# snappergps_board_2_2_0.net
KiCad netlist of a schematic drawn in EAGLE
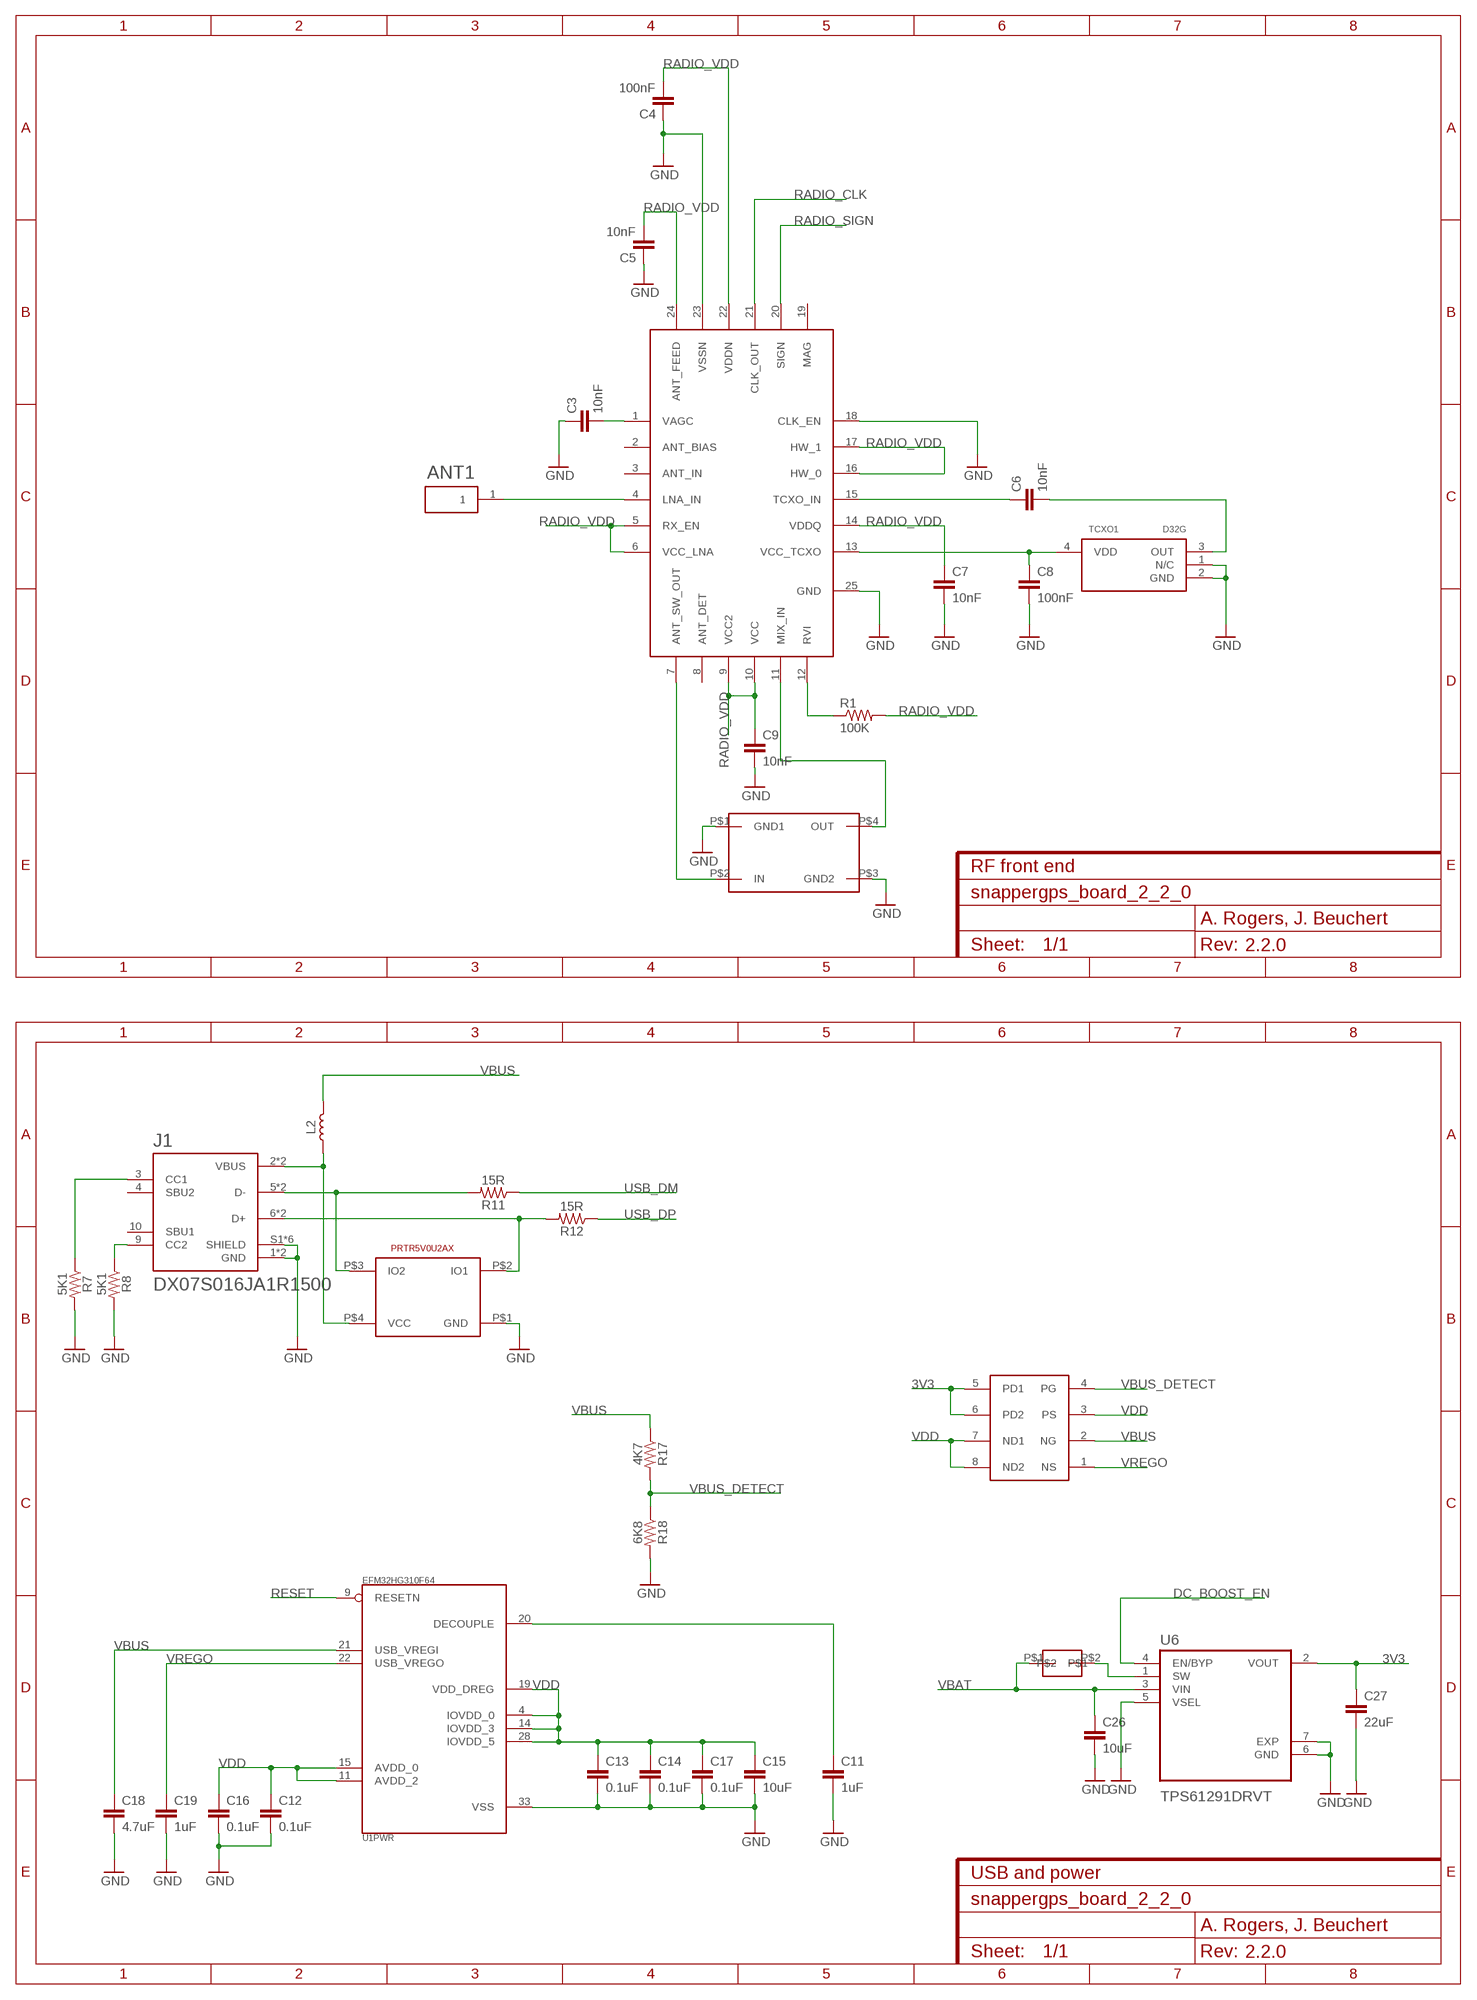
[diagram p0: schematic, sheet 1, part 1 of 2]
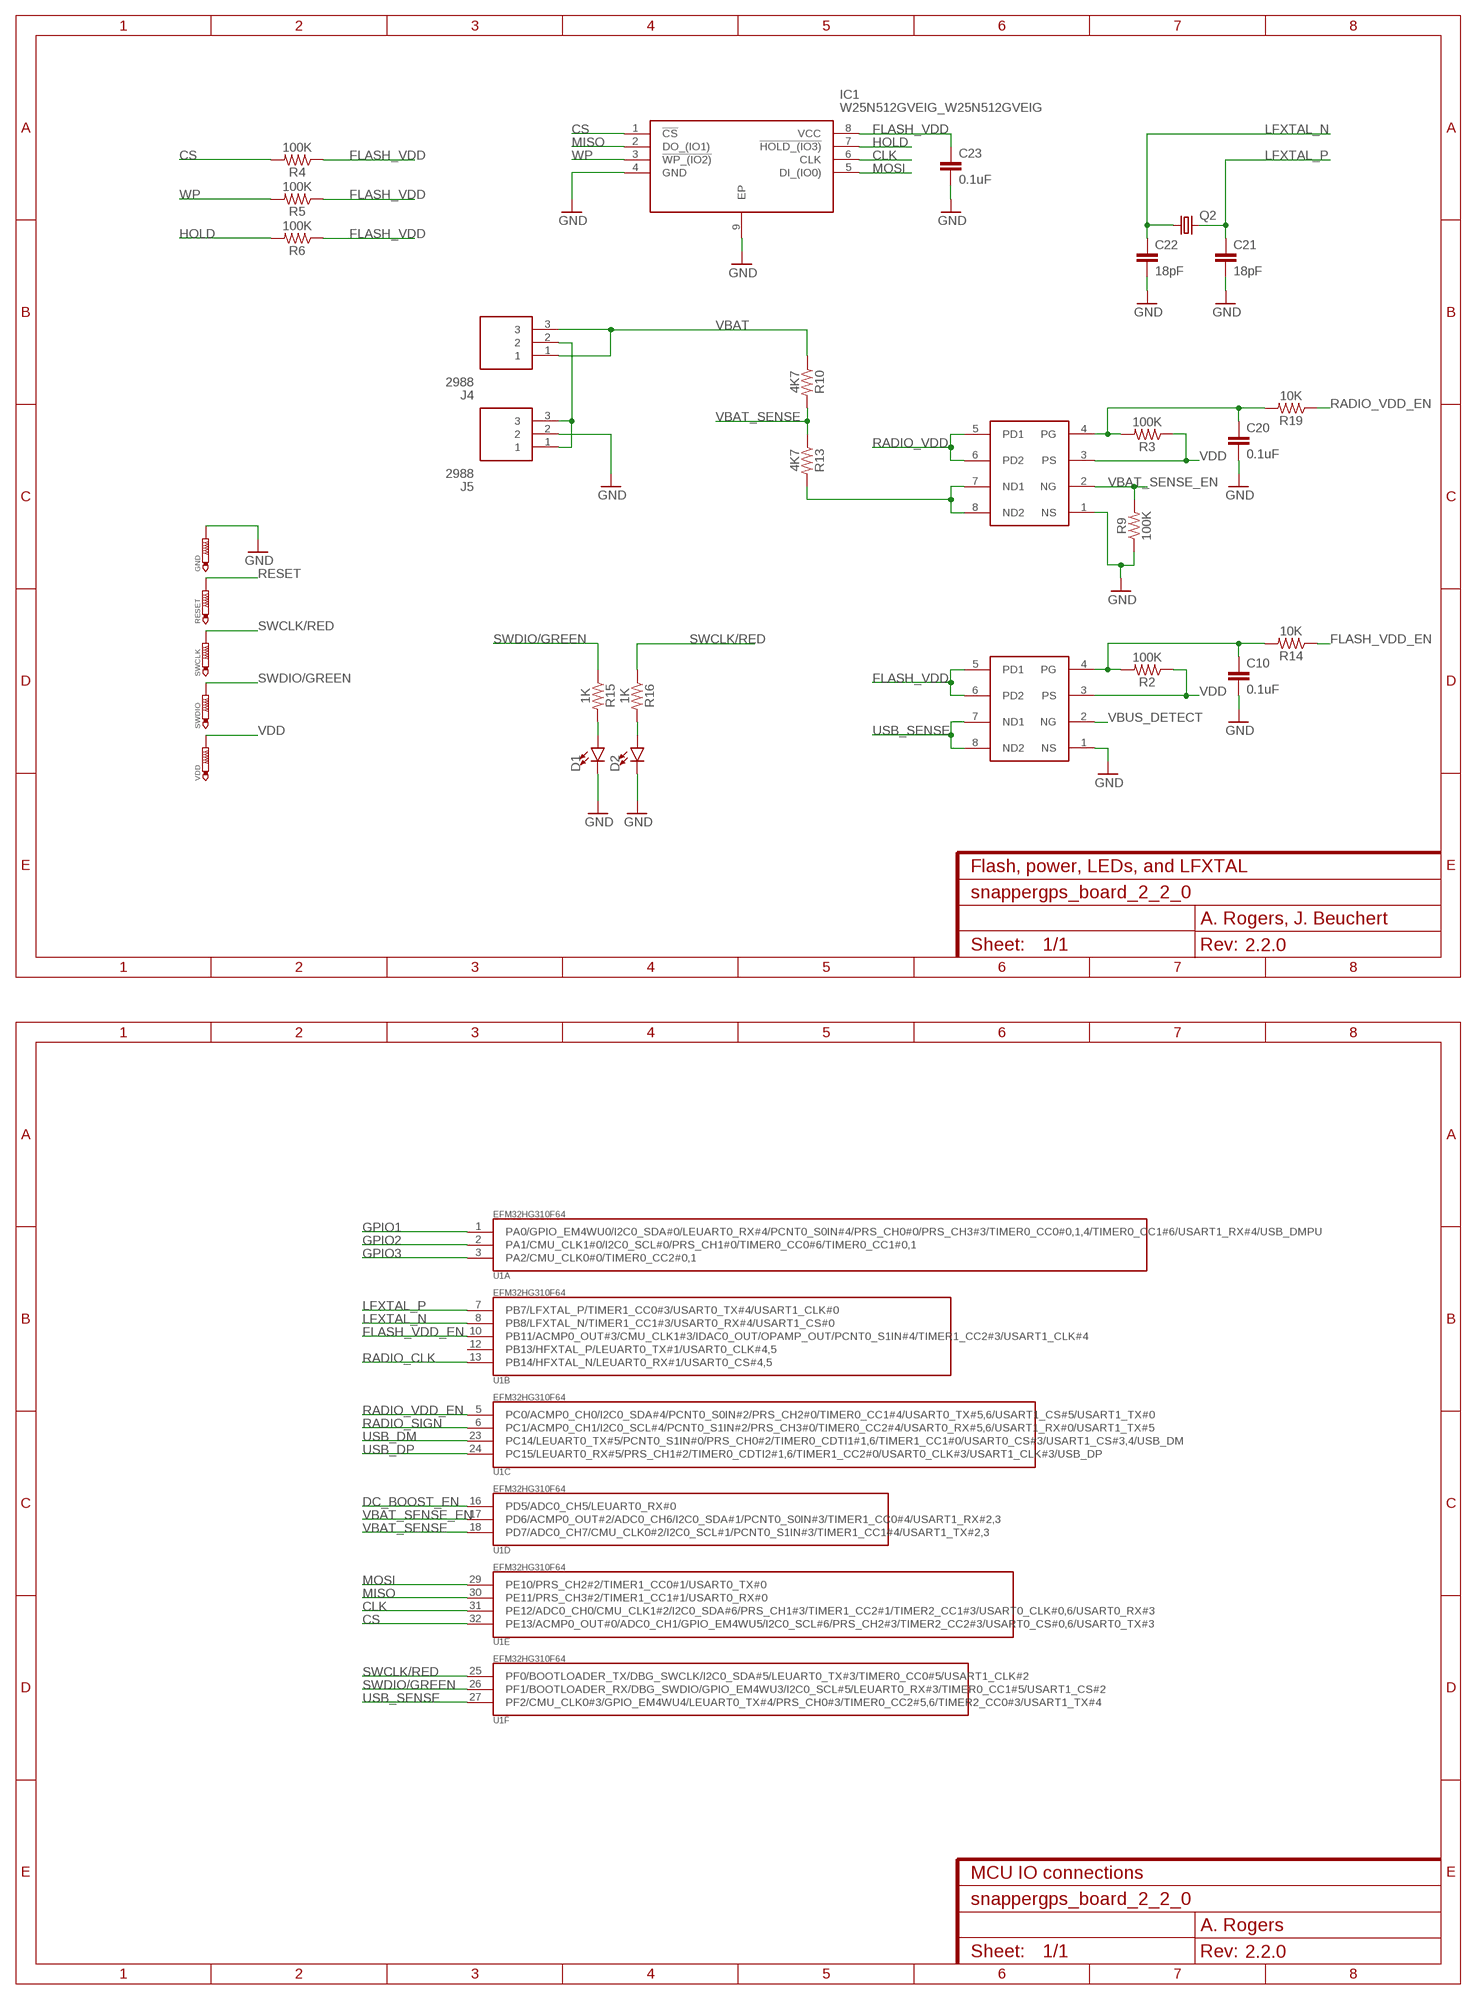
[diagram p1: schematic, sheet 1, part 2 of 2]

(export (version "E")
  (design (tool "Eeschema 10.0.6"))
  (components
    (comp (ref "ANT1")
      (value "GP.1575.25.2.A.02")
      (footprint "eagle-import:GP1575252A02")
      (fields (field (name "MOUSER_PART_NUMBER") "960-GP1575252A02"))
      (libsource (lib "eagle-import") (part "GP.1575.25.2.A.02"))
    )
    (comp (ref "C3")
      (value "10nF")
      (footprint "eagle-import:0402")
      (libsource (lib "eagle-import") (part "CAPACITOR_0402"))
    )
    (comp (ref "C4")
      (value "100nF")
      (footprint "eagle-import:0402")
      (libsource (lib "eagle-import") (part "CAPACITOR_0402"))
    )
    (comp (ref "C5")
      (value "10nF")
      (footprint "eagle-import:0402")
      (libsource (lib "eagle-import") (part "CAPACITOR_0402"))
    )
    (comp (ref "C6")
      (value "10nF")
      (footprint "eagle-import:0402")
      (libsource (lib "eagle-import") (part "CAPACITOR_0402"))
    )
    (comp (ref "C7")
      (value "10nF")
      (footprint "eagle-import:0402")
      (libsource (lib "eagle-import") (part "CAPACITOR_0402"))
    )
    (comp (ref "C8")
      (value "100nF")
      (footprint "eagle-import:0402")
      (libsource (lib "eagle-import") (part "CAPACITOR_0402"))
    )
    (comp (ref "C9")
      (value "10nF")
      (footprint "eagle-import:0402")
      (libsource (lib "eagle-import") (part "CAPACITOR_0402"))
    )
    (comp (ref "C10")
      (value "0.1uF")
      (footprint "eagle-import:0402")
      (libsource (lib "eagle-import") (part "CAPACITOR_0402"))
    )
    (comp (ref "C11")
      (value "1uF")
      (footprint "eagle-import:0603")
      (libsource (lib "eagle-import") (part "CAPACITOR_0603"))
    )
    (comp (ref "C12")
      (value "0.1uF")
      (footprint "eagle-import:0402")
      (libsource (lib "eagle-import") (part "CAPACITOR_0402"))
    )
    (comp (ref "C13")
      (value "0.1uF")
      (footprint "eagle-import:0402")
      (libsource (lib "eagle-import") (part "CAPACITOR_0402"))
    )
    (comp (ref "C14")
      (value "0.1uF")
      (footprint "eagle-import:0402")
      (libsource (lib "eagle-import") (part "CAPACITOR_0402"))
    )
    (comp (ref "C15")
      (value "10uF")
      (footprint "eagle-import:0603")
      (libsource (lib "eagle-import") (part "CAPACITOR_0603"))
    )
    (comp (ref "C16")
      (value "0.1uF")
      (footprint "eagle-import:0402")
      (libsource (lib "eagle-import") (part "CAPACITOR_0402"))
    )
    (comp (ref "C17")
      (value "0.1uF")
      (footprint "eagle-import:0402")
      (libsource (lib "eagle-import") (part "CAPACITOR_0402"))
    )
    (comp (ref "C18")
      (value "4.7uF")
      (footprint "eagle-import:0603")
      (libsource (lib "eagle-import") (part "CAPACITOR_0603"))
    )
    (comp (ref "C19")
      (value "1uF")
      (footprint "eagle-import:0603")
      (libsource (lib "eagle-import") (part "CAPACITOR_0603"))
    )
    (comp (ref "C20")
      (value "0.1uF")
      (footprint "eagle-import:0402")
      (libsource (lib "eagle-import") (part "CAPACITOR_0402"))
    )
    (comp (ref "C21")
      (value "18pF")
      (footprint "eagle-import:0402")
      (libsource (lib "eagle-import") (part "CAPACITOR_0402"))
    )
    (comp (ref "C22")
      (value "18pF")
      (footprint "eagle-import:0402")
      (libsource (lib "eagle-import") (part "CAPACITOR_0402"))
    )
    (comp (ref "C23")
      (value "0.1uF")
      (footprint "eagle-import:0402")
      (libsource (lib "eagle-import") (part "CAPACITOR_0402"))
    )
    (comp (ref "C26")
      (value "10uF")
      (footprint "eagle-import:C0603K")
      (libsource (lib "eagle-import") (part "C-EUC0603K"))
    )
    (comp (ref "C27")
      (value "22uF")
      (footprint "eagle-import:C0603K")
      (libsource (lib "eagle-import") (part "C-EUC0603K"))
    )
    (comp (ref "D1")
      (value "LED0603")
      (footprint "eagle-import:LED-0603")
      (libsource (lib "eagle-import") (part "LED0603"))
    )
    (comp (ref "D2")
      (value "LED0603")
      (footprint "eagle-import:LED-0603")
      (libsource (lib "eagle-import") (part "LED0603"))
    )
    (comp (ref "GND")
      (value "PTR1B1,27")
      (footprint "eagle-import:B1,27")
      (libsource (lib "eagle-import") (part "PTR1B1,27"))
    )
    (comp (ref "IC1")
      (value "W25N512GVEIG_W25N512GVEIG")
      (footprint "eagle-import:W25N512GVEIG_SON127P800X600X80-9N")
      (fields
        (field (name "MANUFACTURER_PART_NUMBER") "W25N512GVEIG")
        (field (name "MOUSER_PART_NUMBER") "454-W25N512GVEIG")
      )
      (libsource (lib "eagle-import") (part "W25N512GVEIG_W25N512GVEIG"))
    )
    (comp (ref "J1")
      (value "DX07S016JA1R1500")
      (footprint "eagle-import:JAE_DX07S016JA1R1500")
      (fields (field (name "MF") "JAE Electronics"))
      (libsource (lib "eagle-import") (part "DX07S016JA1R1500"))
    )
    (comp (ref "J4")
      (value "2988")
      (footprint "eagle-import:2988")
      (fields (field (name "MOUSER_PART_NUMBER") "534-2988"))
      (libsource (lib "eagle-import") (part "2988"))
    )
    (comp (ref "J5")
      (value "2988")
      (footprint "eagle-import:2988")
      (fields (field (name "MOUSER_PART_NUMBER") "534-2988"))
      (libsource (lib "eagle-import") (part "2988"))
    )
    (comp (ref "L2")
      (value "INDUCTOR")
      (footprint "eagle-import:0402")
      (libsource (lib "eagle-import") (part "INDUCTOR"))
    )
    (comp (ref "Q1")
      (value "TT8M1TRAMANDA")
      (footprint "eagle-import:AMANDA_TSST8")
      (libsource (lib "eagle-import") (part "TT8M1TRAMANDA"))
    )
    (comp (ref "Q2")
      (value "CRYSTAL_JTX310")
      (footprint "eagle-import:3.2X1.5")
      (libsource (lib "eagle-import") (part "CRYSTAL_JTX310"))
    )
    (comp (ref "Q3")
      (value "TT8M1TRAMANDA")
      (footprint "eagle-import:AMANDA_TSST8")
      (libsource (lib "eagle-import") (part "TT8M1TRAMANDA"))
    )
    (comp (ref "Q4")
      (value "TT8M1TRAMANDA")
      (footprint "eagle-import:AMANDA_TSST8")
      (libsource (lib "eagle-import") (part "TT8M1TRAMANDA"))
    )
    (comp (ref "R1")
      (value "100K")
      (footprint "eagle-import:0402")
      (libsource (lib "eagle-import") (part "RESISTOR_0402"))
    )
    (comp (ref "R2")
      (value "100K")
      (footprint "eagle-import:0402")
      (libsource (lib "eagle-import") (part "RESISTOR_0402"))
    )
    (comp (ref "R3")
      (value "100K")
      (footprint "eagle-import:0402")
      (libsource (lib "eagle-import") (part "RESISTOR_0402"))
    )
    (comp (ref "R4")
      (value "100K")
      (footprint "eagle-import:0402")
      (libsource (lib "eagle-import") (part "RESISTOR_0402"))
    )
    (comp (ref "R5")
      (value "100K")
      (footprint "eagle-import:0402")
      (libsource (lib "eagle-import") (part "RESISTOR_0402"))
    )
    (comp (ref "R6")
      (value "100K")
      (footprint "eagle-import:0402")
      (libsource (lib "eagle-import") (part "RESISTOR_0402"))
    )
    (comp (ref "R7")
      (value "5K1")
      (footprint "eagle-import:0402")
      (libsource (lib "eagle-import") (part "RESISTOR_0402"))
    )
    (comp (ref "R8")
      (value "5K1")
      (footprint "eagle-import:0402")
      (libsource (lib "eagle-import") (part "RESISTOR_0402"))
    )
    (comp (ref "R9")
      (value "100K")
      (footprint "eagle-import:0402")
      (libsource (lib "eagle-import") (part "RESISTOR_0402"))
    )
    (comp (ref "R10")
      (value "4K7")
      (footprint "eagle-import:0402")
      (libsource (lib "eagle-import") (part "RESISTOR_0402"))
    )
    (comp (ref "R11")
      (value "15R")
      (footprint "eagle-import:0402")
      (libsource (lib "eagle-import") (part "RESISTOR_0402"))
    )
    (comp (ref "R12")
      (value "15R")
      (footprint "eagle-import:0402")
      (libsource (lib "eagle-import") (part "RESISTOR_0402"))
    )
    (comp (ref "R13")
      (value "4K7")
      (footprint "eagle-import:0402")
      (libsource (lib "eagle-import") (part "RESISTOR_0402"))
    )
    (comp (ref "R14")
      (value "10K")
      (footprint "eagle-import:0402")
      (libsource (lib "eagle-import") (part "RESISTOR_0402"))
    )
    (comp (ref "R15")
      (value "1K")
      (footprint "eagle-import:0402")
      (libsource (lib "eagle-import") (part "RESISTOR_0402"))
    )
    (comp (ref "R16")
      (value "1K")
      (footprint "eagle-import:0402")
      (libsource (lib "eagle-import") (part "RESISTOR_0402"))
    )
    (comp (ref "R17")
      (value "4K7")
      (footprint "eagle-import:0402")
      (libsource (lib "eagle-import") (part "RESISTOR_0402"))
    )
    (comp (ref "R18")
      (value "6K8")
      (footprint "eagle-import:0402")
      (libsource (lib "eagle-import") (part "RESISTOR_0402"))
    )
    (comp (ref "R19")
      (value "10K")
      (footprint "eagle-import:0402")
      (libsource (lib "eagle-import") (part "RESISTOR_0402"))
    )
    (comp (ref "RESET")
      (value "PTR1B1,27")
      (footprint "eagle-import:B1,27")
      (libsource (lib "eagle-import") (part "PTR1B1,27"))
    )
    (comp (ref "SAW1")
      (value "SAW_FILTER")
      (footprint "eagle-import:SAW_FILTER")
      (libsource (lib "eagle-import") (part "SAW_FILTER"))
    )
    (comp (ref "SWCLK")
      (value "PTR1B1,27")
      (footprint "eagle-import:B1,27")
      (libsource (lib "eagle-import") (part "PTR1B1,27"))
    )
    (comp (ref "SWDIO")
      (value "PTR1B1,27")
      (footprint "eagle-import:B1,27")
      (libsource (lib "eagle-import") (part "PTR1B1,27"))
    )
    (comp (ref "TCXO1")
      (value "D32G")
      (footprint "eagle-import:D32G")
      (libsource (lib "eagle-import") (part "D32G"))
    )
    (comp (ref "U1")
      (value "EFM32HG310F64")
      (footprint "eagle-import:QFN32")
      (libsource (lib "eagle-import") (part "EFM32HG310F64"))
    )
    (comp (ref "U2")
      (value "RF_CIRCUIT-SE4150L")
      (footprint "eagle-import:QFN50P400X400X90-25N")
      (libsource (lib "eagle-import") (part "RF_CIRCUIT-SE4150L"))
    )
    (comp (ref "U3")
      (value "TVS_DIODE-PRTR5V0U2AX")
      (footprint "eagle-import:TVS_DIODE-PRTR5V0U2AX")
      (libsource (lib "eagle-import") (part "TVS_DIODE-PRTR5V0U2AX"))
    )
    (comp (ref "U6")
      (value "TPS61291DRVT")
      (footprint "eagle-import:SON65P200X200X80-7N")
      (fields (field (name "MF") "Texas Instruments"))
      (libsource (lib "eagle-import") (part "TPS61291DRVT"))
    )
    (comp (ref "U7")
      (value "MDMK2020T3R3MM")
      (footprint "eagle-import:MDMK2020T3R3MM")
      (libsource (lib "eagle-import") (part "MDMK2020T3R3MM"))
    )
    (comp (ref "VDD")
      (value "PTR1B1,27")
      (footprint "eagle-import:B1,27")
      (libsource (lib "eagle-import") (part "PTR1B1,27"))
    )
  )
  (nets
    (net (code "1") (name "/3V3") (class "Default")
      (node (ref "C27") (pin "1") (pinfunction "1_1") (pintype "passive"))
      (node (ref "Q4") (pin "5") (pinfunction "PD1_5") (pintype "bidirectional"))
      (node (ref "Q4") (pin "6") (pinfunction "PD2_6") (pintype "bidirectional"))
      (node (ref "U6") (pin "2") (pinfunction "VOUT_2") (pintype "output"))
    )
    (net (code "2") (name "/CLK") (class "Default")
      (node (ref "IC1") (pin "6") (pinfunction "CLK_6") (pintype "bidirectional"))
      (node (ref "U1") (pin "31") (pinfunction "PE12/ADC0_CH0/CMU_CLK1#2/I2C0_SDA#6/PRS_CH1#3/TIMER1_CC2#1/TIMER2_CC1#3/USART0_CLK#0,6/USART0_RX#3_31") (pintype "bidirectional"))
    )
    (net (code "3") (name "/CS") (class "Default")
      (node (ref "IC1") (pin "1") (pinfunction "~{CS}_1") (pintype "bidirectional"))
      (node (ref "R4") (pin "2") (pinfunction "2_2") (pintype "passive"))
      (node (ref "U1") (pin "32") (pinfunction "PE13/ACMP0_OUT#0/ADC0_CH1/GPIO_EM4WU5/I2C0_SCL#6/PRS_CH2#3/TIMER2_CC2#3/USART0_CS#0,6/USART0_TX#3_32") (pintype "bidirectional"))
    )
    (net (code "4") (name "/DC_BOOST_EN") (class "Default")
      (node (ref "U1") (pin "16") (pinfunction "PD5/ADC0_CH5/LEUART0_RX#0_16") (pintype "bidirectional"))
      (node (ref "U6") (pin "4") (pinfunction "EN/BYP_4") (pintype "input"))
    )
    (net (code "5") (name "/FLASH_VDD") (class "Default")
      (node (ref "C23") (pin "1") (pinfunction "1_1") (pintype "passive"))
      (node (ref "IC1") (pin "8") (pinfunction "VCC_8") (pintype "bidirectional"))
      (node (ref "Q3") (pin "5") (pinfunction "PD1_5") (pintype "bidirectional"))
      (node (ref "Q3") (pin "6") (pinfunction "PD2_6") (pintype "bidirectional"))
      (node (ref "R4") (pin "1") (pinfunction "1_1") (pintype "passive"))
      (node (ref "R5") (pin "1") (pinfunction "1_1") (pintype "passive"))
      (node (ref "R6") (pin "1") (pinfunction "1_1") (pintype "passive"))
    )
    (net (code "6") (name "/FLASH_VDD_EN") (class "Default")
      (node (ref "R14") (pin "1") (pinfunction "1_1") (pintype "passive"))
      (node (ref "U1") (pin "10") (pinfunction "PB11/ACMP0_OUT#3/CMU_CLK1#3/IDAC0_OUT/OPAMP_OUT/PCNT0_S1IN#4/TIMER1_CC2#3/USART1_CLK#4_10") (pintype "bidirectional"))
    )
    (net (code "7") (name "/GPIO1") (class "Default")
      (node (ref "U1") (pin "1") (pinfunction "PA0/GPIO_EM4WU0/I2C0_SDA#0/LEUART0_RX#4/PCNT0_S0IN#4/PRS_CH0#0/PRS_CH3#3/TIMER0_CC0#0,1,4/TIMER0_CC1#6/USART1_RX#4/USB_DMPU_1") (pintype "bidirectional"))
    )
    (net (code "8") (name "/GPIO2") (class "Default")
      (node (ref "U1") (pin "2") (pinfunction "PA1/CMU_CLK1#0/I2C0_SCL#0/PRS_CH1#0/TIMER0_CC0#6/TIMER0_CC1#0,1_2") (pintype "bidirectional"))
    )
    (net (code "9") (name "/GPIO3") (class "Default")
      (node (ref "U1") (pin "3") (pinfunction "PA2/CMU_CLK0#0/TIMER0_CC2#0,1_3") (pintype "bidirectional"))
    )
    (net (code "10") (name "/HOLD") (class "Default")
      (node (ref "IC1") (pin "7") (pinfunction "~{HOLD_(IO3})_7") (pintype "bidirectional"))
      (node (ref "R6") (pin "2") (pinfunction "2_2") (pintype "passive"))
    )
    (net (code "11") (name "/LFXTAL_N") (class "Default")
      (node (ref "C22") (pin "1") (pinfunction "1_1") (pintype "passive"))
      (node (ref "Q2") (pin "1") (pinfunction "1_1") (pintype "passive"))
      (node (ref "U1") (pin "8") (pinfunction "PB8/LFXTAL_N/TIMER1_CC1#3/USART0_RX#4/USART1_CS#0_8") (pintype "bidirectional"))
    )
    (net (code "12") (name "/LFXTAL_P") (class "Default")
      (node (ref "C21") (pin "1") (pinfunction "1_1") (pintype "passive"))
      (node (ref "Q2") (pin "2") (pinfunction "2_2") (pintype "passive"))
      (node (ref "U1") (pin "7") (pinfunction "PB7/LFXTAL_P/TIMER1_CC0#3/USART0_TX#4/USART1_CLK#0_7") (pintype "bidirectional"))
    )
    (net (code "13") (name "/MISO") (class "Default")
      (node (ref "IC1") (pin "2") (pinfunction "DO_(IO1)_2") (pintype "bidirectional"))
      (node (ref "U1") (pin "30") (pinfunction "PE11/PRS_CH3#2/TIMER1_CC1#1/USART0_RX#0_30") (pintype "bidirectional"))
    )
    (net (code "14") (name "/MOSI") (class "Default")
      (node (ref "IC1") (pin "5") (pinfunction "DI_(IO0)_5") (pintype "bidirectional"))
      (node (ref "U1") (pin "29") (pinfunction "PE10/PRS_CH2#2/TIMER1_CC0#1/USART0_TX#0_29") (pintype "bidirectional"))
    )
    (net (code "15") (name "/RADIO_CLK") (class "Default")
      (node (ref "U1") (pin "13") (pinfunction "PB14/HFXTAL_N/LEUART0_RX#1/USART0_CS#4,5_13") (pintype "bidirectional"))
      (node (ref "U2") (pin "21") (pinfunction "CLK_OUT_21") (pintype "bidirectional"))
    )
    (net (code "16") (name "/RADIO_SIGN") (class "Default")
      (node (ref "U1") (pin "6") (pinfunction "PC1/ACMP0_CH1/I2C0_SCL#4/PCNT0_S1IN#2/PRS_CH3#0/TIMER0_CC2#4/USART0_RX#5,6/USART1_RX#0/USART1_TX#5_6") (pintype "bidirectional"))
      (node (ref "U2") (pin "20") (pinfunction "SIGN_20") (pintype "bidirectional"))
    )
    (net (code "17") (name "/RADIO_VDD") (class "Default")
      (node (ref "C4") (pin "2") (pinfunction "2_2") (pintype "passive"))
      (node (ref "C5") (pin "2") (pinfunction "2_2") (pintype "passive"))
      (node (ref "C7") (pin "1") (pinfunction "1_1") (pintype "passive"))
      (node (ref "C9") (pin "1") (pinfunction "1_1") (pintype "passive"))
      (node (ref "Q1") (pin "5") (pinfunction "PD1_5") (pintype "bidirectional"))
      (node (ref "Q1") (pin "6") (pinfunction "PD2_6") (pintype "bidirectional"))
      (node (ref "R1") (pin "2") (pinfunction "2_2") (pintype "passive"))
      (node (ref "U2") (pin "10") (pinfunction "VCC_10") (pintype "bidirectional"))
      (node (ref "U2") (pin "14") (pinfunction "VDDQ_14") (pintype "bidirectional"))
      (node (ref "U2") (pin "16") (pinfunction "HW_0_16") (pintype "bidirectional"))
      (node (ref "U2") (pin "17") (pinfunction "HW_1_17") (pintype "bidirectional"))
      (node (ref "U2") (pin "22") (pinfunction "VDDN_22") (pintype "bidirectional"))
      (node (ref "U2") (pin "24") (pinfunction "ANT_FEED_24") (pintype "bidirectional"))
      (node (ref "U2") (pin "5") (pinfunction "RX_EN_5") (pintype "bidirectional"))
      (node (ref "U2") (pin "6") (pinfunction "VCC_LNA_6") (pintype "bidirectional"))
      (node (ref "U2") (pin "9") (pinfunction "VCC2_9") (pintype "bidirectional"))
    )
    (net (code "18") (name "/RADIO_VDD_EN") (class "Default")
      (node (ref "R19") (pin "1") (pinfunction "1_1") (pintype "passive"))
      (node (ref "U1") (pin "5") (pinfunction "PC0/ACMP0_CH0/I2C0_SDA#4/PCNT0_S0IN#2/PRS_CH2#0/TIMER0_CC1#4/USART0_TX#5,6/USART1_CS#5/USART1_TX#0_5") (pintype "bidirectional"))
    )
    (net (code "19") (name "/RESET") (class "Default")
      (node (ref "RESET") (pin "TP") (pinfunction "TP_TP") (pintype "input"))
      (node (ref "U1") (pin "9") (pinfunction "RESETN_9") (pintype "passive"))
    )
    (net (code "20") (name "/SWCLK{slash}RED") (class "Default")
      (node (ref "R16") (pin "1") (pinfunction "1_1") (pintype "passive"))
      (node (ref "SWCLK") (pin "TP") (pinfunction "TP_TP") (pintype "input"))
      (node (ref "U1") (pin "25") (pinfunction "PF0/BOOTLOADER_TX/DBG_SWCLK/I2C0_SDA#5/LEUART0_TX#3/TIMER0_CC0#5/USART1_CLK#2_25") (pintype "bidirectional"))
    )
    (net (code "21") (name "/SWDIO{slash}GREEN") (class "Default")
      (node (ref "R15") (pin "1") (pinfunction "1_1") (pintype "passive"))
      (node (ref "SWDIO") (pin "TP") (pinfunction "TP_TP") (pintype "input"))
      (node (ref "U1") (pin "26") (pinfunction "PF1/BOOTLOADER_RX/DBG_SWDIO/GPIO_EM4WU3/I2C0_SCL#5/LEUART0_RX#3/TIMER0_CC1#5/USART1_CS#2_26") (pintype "bidirectional"))
    )
    (net (code "22") (name "/USB_DM") (class "Default")
      (node (ref "R11") (pin "1") (pinfunction "1_1") (pintype "passive"))
      (node (ref "U1") (pin "23") (pinfunction "PC14/LEUART0_TX#5/PCNT0_S1IN#0/PRS_CH0#2/TIMER0_CDTI1#1,6/TIMER1_CC1#0/USART0_CS#3/USART1_CS#3,4/USB_DM_23") (pintype "bidirectional"))
    )
    (net (code "23") (name "/USB_DP") (class "Default")
      (node (ref "R12") (pin "1") (pinfunction "1_1") (pintype "passive"))
      (node (ref "U1") (pin "24") (pinfunction "PC15/LEUART0_RX#5/PRS_CH1#2/TIMER0_CDTI2#1,6/TIMER1_CC2#0/USART0_CLK#3/USART1_CLK#3/USB_DP_24") (pintype "bidirectional"))
    )
    (net (code "24") (name "/USB_SENSE") (class "Default")
      (node (ref "Q3") (pin "7") (pinfunction "ND1_7") (pintype "bidirectional"))
      (node (ref "Q3") (pin "8") (pinfunction "ND2_8") (pintype "bidirectional"))
      (node (ref "U1") (pin "27") (pinfunction "PF2/CMU_CLK0#3/GPIO_EM4WU4/LEUART0_TX#4/PRS_CH0#3/TIMER0_CC2#5,6/TIMER2_CC0#3/USART1_TX#4_27") (pintype "bidirectional"))
    )
    (net (code "25") (name "/VBAT") (class "Default")
      (node (ref "C26") (pin "1") (pinfunction "1_1") (pintype "passive"))
      (node (ref "J4") (pin "1") (pinfunction "1_1") (pintype "bidirectional"))
      (node (ref "J4") (pin "3") (pinfunction "3_3") (pintype "bidirectional"))
      (node (ref "R10") (pin "1") (pinfunction "1_1") (pintype "passive"))
      (node (ref "U6") (pin "3") (pinfunction "VIN_3") (pintype "input"))
      (node (ref "U7") (pin "P$1") (pinfunction "P$1_P$1") (pintype "bidirectional"))
    )
    (net (code "26") (name "/VBAT_SENSE") (class "Default")
      (node (ref "R10") (pin "2") (pinfunction "2_2") (pintype "passive"))
      (node (ref "R13") (pin "1") (pinfunction "1_1") (pintype "passive"))
      (node (ref "U1") (pin "18") (pinfunction "PD7/ADC0_CH7/CMU_CLK0#2/I2C0_SCL#1/PCNT0_S1IN#3/TIMER1_CC1#4/USART1_TX#2,3_18") (pintype "bidirectional"))
    )
    (net (code "27") (name "/VBAT_SENSE_EN") (class "Default")
      (node (ref "Q1") (pin "2") (pinfunction "NG_2") (pintype "bidirectional"))
      (node (ref "R9") (pin "2") (pinfunction "2_2") (pintype "passive"))
      (node (ref "U1") (pin "17") (pinfunction "PD6/ACMP0_OUT#2/ADC0_CH6/I2C0_SDA#1/PCNT0_S0IN#3/TIMER1_CC0#4/USART1_RX#2,3_17") (pintype "bidirectional"))
    )
    (net (code "28") (name "/VBUS") (class "Default")
      (node (ref "C18") (pin "1") (pinfunction "1_1") (pintype "passive"))
      (node (ref "L2") (pin "2") (pinfunction "2_2") (pintype "passive"))
      (node (ref "Q4") (pin "2") (pinfunction "NG_2") (pintype "bidirectional"))
      (node (ref "R17") (pin "1") (pinfunction "1_1") (pintype "passive"))
      (node (ref "U1") (pin "21") (pinfunction "USB_VREGI_21") (pintype "power_in"))
    )
    (net (code "29") (name "/VBUS_DETECT") (class "Default")
      (node (ref "Q3") (pin "2") (pinfunction "NG_2") (pintype "bidirectional"))
      (node (ref "Q4") (pin "4") (pinfunction "PG_4") (pintype "bidirectional"))
      (node (ref "R17") (pin "2") (pinfunction "2_2") (pintype "passive"))
      (node (ref "R18") (pin "1") (pinfunction "1_1") (pintype "passive"))
    )
    (net (code "30") (name "/VDD") (class "Default")
      (node (ref "C12") (pin "1") (pinfunction "1_1") (pintype "passive"))
      (node (ref "C13") (pin "1") (pinfunction "1_1") (pintype "passive"))
      (node (ref "C14") (pin "1") (pinfunction "1_1") (pintype "passive"))
      (node (ref "C15") (pin "1") (pinfunction "1_1") (pintype "passive"))
      (node (ref "C16") (pin "1") (pinfunction "1_1") (pintype "passive"))
      (node (ref "C17") (pin "1") (pinfunction "1_1") (pintype "passive"))
      (node (ref "Q1") (pin "3") (pinfunction "PS_3") (pintype "bidirectional"))
      (node (ref "Q3") (pin "3") (pinfunction "PS_3") (pintype "bidirectional"))
      (node (ref "Q4") (pin "3") (pinfunction "PS_3") (pintype "bidirectional"))
      (node (ref "Q4") (pin "7") (pinfunction "ND1_7") (pintype "bidirectional"))
      (node (ref "Q4") (pin "8") (pinfunction "ND2_8") (pintype "bidirectional"))
      (node (ref "R2") (pin "1") (pinfunction "1_1") (pintype "passive"))
      (node (ref "R3") (pin "1") (pinfunction "1_1") (pintype "passive"))
      (node (ref "U1") (pin "11") (pinfunction "AVDD_2_11") (pintype "power_in"))
      (node (ref "U1") (pin "14") (pinfunction "IOVDD_3_14") (pintype "power_in"))
      (node (ref "U1") (pin "15") (pinfunction "AVDD_0_15") (pintype "power_in"))
      (node (ref "U1") (pin "19") (pinfunction "VDD_DREG_19") (pintype "power_in"))
      (node (ref "U1") (pin "28") (pinfunction "IOVDD_5_28") (pintype "power_in"))
      (node (ref "U1") (pin "4") (pinfunction "IOVDD_0_4") (pintype "power_in"))
      (node (ref "VDD") (pin "TP") (pinfunction "TP_TP") (pintype "input"))
    )
    (net (code "31") (name "/VREGO") (class "Default")
      (node (ref "C19") (pin "1") (pinfunction "1_1") (pintype "passive"))
      (node (ref "Q4") (pin "1") (pinfunction "NS_1") (pintype "bidirectional"))
      (node (ref "U1") (pin "22") (pinfunction "USB_VREGO_22") (pintype "power_in"))
    )
    (net (code "32") (name "/WP") (class "Default")
      (node (ref "IC1") (pin "3") (pinfunction "~{WP_(IO2})_3") (pintype "bidirectional"))
      (node (ref "R5") (pin "2") (pinfunction "2_2") (pintype "passive"))
    )
    (net (code "33") (name "GND") (class "Default")
      (node (ref "C10") (pin "2") (pinfunction "2_2") (pintype "passive"))
      (node (ref "C11") (pin "2") (pinfunction "2_2") (pintype "passive"))
      (node (ref "C12") (pin "2") (pinfunction "2_2") (pintype "passive"))
      (node (ref "C13") (pin "2") (pinfunction "2_2") (pintype "passive"))
      (node (ref "C14") (pin "2") (pinfunction "2_2") (pintype "passive"))
      (node (ref "C15") (pin "2") (pinfunction "2_2") (pintype "passive"))
      (node (ref "C16") (pin "2") (pinfunction "2_2") (pintype "passive"))
      (node (ref "C17") (pin "2") (pinfunction "2_2") (pintype "passive"))
      (node (ref "C18") (pin "2") (pinfunction "2_2") (pintype "passive"))
      (node (ref "C19") (pin "2") (pinfunction "2_2") (pintype "passive"))
      (node (ref "C20") (pin "2") (pinfunction "2_2") (pintype "passive"))
      (node (ref "C21") (pin "2") (pinfunction "2_2") (pintype "passive"))
      (node (ref "C22") (pin "2") (pinfunction "2_2") (pintype "passive"))
      (node (ref "C23") (pin "2") (pinfunction "2_2") (pintype "passive"))
      (node (ref "C26") (pin "2") (pinfunction "2_2") (pintype "passive"))
      (node (ref "C27") (pin "2") (pinfunction "2_2") (pintype "passive"))
      (node (ref "C3") (pin "1") (pinfunction "1_1") (pintype "passive"))
      (node (ref "C4") (pin "1") (pinfunction "1_1") (pintype "passive"))
      (node (ref "C5") (pin "1") (pinfunction "1_1") (pintype "passive"))
      (node (ref "C7") (pin "2") (pinfunction "2_2") (pintype "passive"))
      (node (ref "C8") (pin "2") (pinfunction "2_2") (pintype "passive"))
      (node (ref "C9") (pin "2") (pinfunction "2_2") (pintype "passive"))
      (node (ref "D1") (pin "C") (pinfunction "C_C") (pintype "passive"))
      (node (ref "D2") (pin "C") (pinfunction "C_C") (pintype "passive"))
      (node (ref "GND") (pin "TP") (pinfunction "TP_TP") (pintype "input"))
      (node (ref "IC1") (pin "4") (pinfunction "GND_4") (pintype "bidirectional"))
      (node (ref "IC1") (pin "9") (pinfunction "EP_9") (pintype "bidirectional"))
      (node (ref "J1") (pin "1") (pinfunction "GND_1") (pintype "power_in"))
      (node (ref "J1") (pin "12") (pinfunction "GND_12") (pintype "power_in"))
      (node (ref "J1") (pin "S1") (pinfunction "SHIELD_S1") (pintype "passive"))
      (node (ref "J1") (pin "S2") (pinfunction "SHIELD_S2") (pintype "passive"))
      (node (ref "J1") (pin "S3") (pinfunction "SHIELD_S3") (pintype "passive"))
      (node (ref "J1") (pin "S4") (pinfunction "SHIELD_S4") (pintype "passive"))
      (node (ref "J1") (pin "S5") (pinfunction "SHIELD_S5") (pintype "passive"))
      (node (ref "J1") (pin "S6") (pinfunction "SHIELD_S6") (pintype "passive"))
      (node (ref "J5") (pin "2") (pinfunction "2_2") (pintype "bidirectional"))
      (node (ref "Q1") (pin "1") (pinfunction "NS_1") (pintype "bidirectional"))
      (node (ref "Q3") (pin "1") (pinfunction "NS_1") (pintype "bidirectional"))
      (node (ref "R18") (pin "2") (pinfunction "2_2") (pintype "passive"))
      (node (ref "R7") (pin "2") (pinfunction "2_2") (pintype "passive"))
      (node (ref "R8") (pin "2") (pinfunction "2_2") (pintype "passive"))
      (node (ref "R9") (pin "1") (pinfunction "1_1") (pintype "passive"))
      (node (ref "SAW1") (pin "P$1") (pinfunction "GND1_P$1") (pintype "bidirectional"))
      (node (ref "SAW1") (pin "P$3") (pinfunction "GND2_P$3") (pintype "bidirectional"))
      (node (ref "TCXO1") (pin "1") (pinfunction "N/C_1") (pintype "bidirectional"))
      (node (ref "TCXO1") (pin "2") (pinfunction "GND_2") (pintype "bidirectional"))
      (node (ref "U1") (pin "33") (pinfunction "VSS_33") (pintype "power_in"))
      (node (ref "U2") (pin "18") (pinfunction "CLK_EN_18") (pintype "bidirectional"))
      (node (ref "U2") (pin "23") (pinfunction "VSSN_23") (pintype "bidirectional"))
      (node (ref "U2") (pin "25") (pinfunction "GND_25") (pintype "bidirectional"))
      (node (ref "U3") (pin "P$1") (pinfunction "GND_P$1") (pintype "bidirectional"))
      (node (ref "U6") (pin "5") (pinfunction "VSEL_5") (pintype "input"))
      (node (ref "U6") (pin "6") (pinfunction "GND_6") (pintype "power_in"))
      (node (ref "U6") (pin "7") (pinfunction "EXP_7") (pintype "power_in"))
    )
    (net (code "34") (name "Net-(D1-PadA)") (class "Default")
      (node (ref "D1") (pin "A") (pinfunction "A_A") (pintype "passive"))
      (node (ref "R15") (pin "2") (pinfunction "2_2") (pintype "passive"))
    )
    (net (code "35") (name "Net-(D2-PadA)") (class "Default")
      (node (ref "D2") (pin "A") (pinfunction "A_A") (pintype "passive"))
      (node (ref "R16") (pin "2") (pinfunction "2_2") (pintype "passive"))
    )
    (net (code "36") (name "Net-(J1-CC1)") (class "Default")
      (node (ref "J1") (pin "3") (pinfunction "CC1_3") (pintype "passive"))
      (node (ref "R7") (pin "1") (pinfunction "1_1") (pintype "passive"))
    )
    (net (code "37") (name "Net-(J1-CC2)") (class "Default")
      (node (ref "J1") (pin "9") (pinfunction "CC2_9") (pintype "passive"))
      (node (ref "R8") (pin "1") (pinfunction "1_1") (pintype "passive"))
    )
    (net (code "38") (name "Net-(J4-Pad2)") (class "Default")
      (node (ref "J4") (pin "2") (pinfunction "2_2") (pintype "bidirectional"))
      (node (ref "J5") (pin "1") (pinfunction "1_1") (pintype "bidirectional"))
      (node (ref "J5") (pin "3") (pinfunction "3_3") (pintype "bidirectional"))
    )
    (net (code "39") (name "Net-(Q1-ND1)") (class "Default")
      (node (ref "Q1") (pin "7") (pinfunction "ND1_7") (pintype "bidirectional"))
      (node (ref "Q1") (pin "8") (pinfunction "ND2_8") (pintype "bidirectional"))
      (node (ref "R13") (pin "2") (pinfunction "2_2") (pintype "passive"))
    )
    (net (code "40") (name "Net-(Q1-PG)") (class "Default")
      (node (ref "C20") (pin "1") (pinfunction "1_1") (pintype "passive"))
      (node (ref "Q1") (pin "4") (pinfunction "PG_4") (pintype "bidirectional"))
      (node (ref "R19") (pin "2") (pinfunction "2_2") (pintype "passive"))
      (node (ref "R3") (pin "2") (pinfunction "2_2") (pintype "passive"))
    )
    (net (code "41") (name "Net-(Q3-PG)") (class "Default")
      (node (ref "C10") (pin "1") (pinfunction "1_1") (pintype "passive"))
      (node (ref "Q3") (pin "4") (pinfunction "PG_4") (pintype "bidirectional"))
      (node (ref "R14") (pin "2") (pinfunction "2_2") (pintype "passive"))
      (node (ref "R2") (pin "2") (pinfunction "2_2") (pintype "passive"))
    )
    (net (code "42") (name "Net-(SAW1-IN)") (class "Default")
      (node (ref "SAW1") (pin "P$2") (pinfunction "IN_P$2") (pintype "bidirectional"))
      (node (ref "U2") (pin "7") (pinfunction "ANT_SW_OUT_7") (pintype "bidirectional"))
    )
    (net (code "43") (name "Net-(SAW1-OUT)") (class "Default")
      (node (ref "SAW1") (pin "P$4") (pinfunction "OUT_P$4") (pintype "bidirectional"))
      (node (ref "U2") (pin "11") (pinfunction "MIX_IN_11") (pintype "bidirectional"))
    )
    (net (code "44") (name "Net-(TCXO1-OUT)") (class "Default")
      (node (ref "C6") (pin "2") (pinfunction "2_2") (pintype "passive"))
      (node (ref "TCXO1") (pin "3") (pinfunction "OUT_3") (pintype "bidirectional"))
    )
    (net (code "45") (name "Net-(TCXO1-VDD)") (class "Default")
      (node (ref "C8") (pin "1") (pinfunction "1_1") (pintype "passive"))
      (node (ref "TCXO1") (pin "4") (pinfunction "VDD_4") (pintype "bidirectional"))
      (node (ref "U2") (pin "13") (pinfunction "VCC_TCXO_13") (pintype "bidirectional"))
    )
    (net (code "46") (name "Net-(U1G-DECOUPLE)") (class "Default")
      (node (ref "C11") (pin "1") (pinfunction "1_1") (pintype "passive"))
      (node (ref "U1") (pin "20") (pinfunction "DECOUPLE_20") (pintype "power_in"))
    )
    (net (code "47") (name "Net-(U2-LNA_IN)") (class "Default")
      (node (ref "ANT1") (pin "1") (pinfunction "1_1") (pintype "bidirectional"))
      (node (ref "U2") (pin "4") (pinfunction "LNA_IN_4") (pintype "bidirectional"))
    )
    (net (code "48") (name "Net-(U2-RVI)") (class "Default")
      (node (ref "R1") (pin "1") (pinfunction "1_1") (pintype "passive"))
      (node (ref "U2") (pin "12") (pinfunction "RVI_12") (pintype "bidirectional"))
    )
    (net (code "49") (name "Net-(U2-TCXO_IN)") (class "Default")
      (node (ref "C6") (pin "1") (pinfunction "1_1") (pintype "passive"))
      (node (ref "U2") (pin "15") (pinfunction "TCXO_IN_15") (pintype "bidirectional"))
    )
    (net (code "50") (name "Net-(U2-VAGC)") (class "Default")
      (node (ref "C3") (pin "2") (pinfunction "2_2") (pintype "passive"))
      (node (ref "U2") (pin "1") (pinfunction "VAGC_1") (pintype "bidirectional"))
    )
    (net (code "51") (name "Net-(U3-IO1)") (class "Default")
      (node (ref "J1") (pin "6") (pinfunction "D+_6") (pintype "passive"))
      (node (ref "J1") (pin "7") (pinfunction "D+_7") (pintype "passive"))
      (node (ref "R12") (pin "2") (pinfunction "2_2") (pintype "passive"))
      (node (ref "U3") (pin "P$2") (pinfunction "IO1_P$2") (pintype "bidirectional"))
    )
    (net (code "52") (name "Net-(U3-IO2)") (class "Default")
      (node (ref "J1") (pin "5") (pinfunction "D-_5") (pintype "passive"))
      (node (ref "J1") (pin "8") (pinfunction "D-_8") (pintype "passive"))
      (node (ref "R11") (pin "2") (pinfunction "2_2") (pintype "passive"))
      (node (ref "U3") (pin "P$3") (pinfunction "IO2_P$3") (pintype "bidirectional"))
    )
    (net (code "53") (name "Net-(U3-VCC)") (class "Default")
      (node (ref "J1") (pin "11") (pinfunction "VBUS_11") (pintype "power_in"))
      (node (ref "J1") (pin "2") (pinfunction "VBUS_2") (pintype "power_in"))
      (node (ref "L2") (pin "1") (pinfunction "1_1") (pintype "passive"))
      (node (ref "U3") (pin "P$4") (pinfunction "VCC_P$4") (pintype "bidirectional"))
    )
    (net (code "54") (name "Net-(U6-SW)") (class "Default")
      (node (ref "U6") (pin "1") (pinfunction "SW_1") (pintype "input"))
      (node (ref "U7") (pin "P$2") (pinfunction "P$2_P$2") (pintype "bidirectional"))
    )
    (net (code "55") (name "unconnected-(J1-SBU1-Pad10)") (class "Default")
      (node (ref "J1") (pin "10") (pinfunction "SBU1_10") (pintype "passive"))
    )
    (net (code "56") (name "unconnected-(J1-SBU2-Pad4)") (class "Default")
      (node (ref "J1") (pin "4") (pinfunction "SBU2_4") (pintype "passive"))
    )
    (net (code "57") (name "unconnected-(U1B-PB13{slash}HFXTAL_P{slash}LEUART0_TX#1{slash}USART0_CLK#4,5-Pad12)") (class "Default")
      (node (ref "U1") (pin "12") (pinfunction "PB13/HFXTAL_P/LEUART0_TX#1/USART0_CLK#4,5_12") (pintype "bidirectional"))
    )
    (net (code "58") (name "unconnected-(U2-ANT_BIAS-Pad2)") (class "Default")
      (node (ref "U2") (pin "2") (pinfunction "ANT_BIAS_2") (pintype "bidirectional"))
    )
    (net (code "59") (name "unconnected-(U2-ANT_DET-Pad8)") (class "Default")
      (node (ref "U2") (pin "8") (pinfunction "ANT_DET_8") (pintype "bidirectional"))
    )
    (net (code "60") (name "unconnected-(U2-ANT_IN-Pad3)") (class "Default")
      (node (ref "U2") (pin "3") (pinfunction "ANT_IN_3") (pintype "bidirectional"))
    )
    (net (code "61") (name "unconnected-(U2-MAG-Pad19)") (class "Default")
      (node (ref "U2") (pin "19") (pinfunction "MAG_19") (pintype "bidirectional"))
    )
  )
)
